# output_filter.net
KiCad netlist of a schematic drawn in Altium Designer
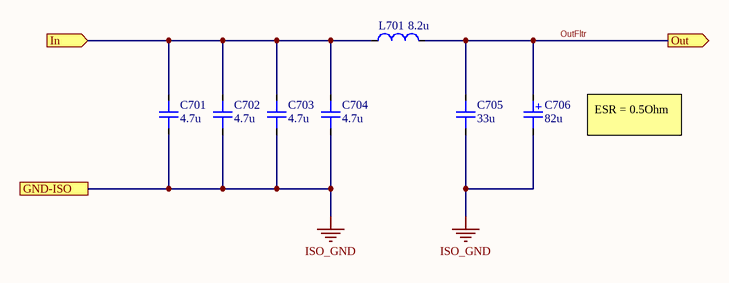
[diagram p0: output_filter.SchDoc]

(export (version "E")
  (design (tool "Eeschema 10.0.6"))
  (components
    (comp (ref "C701")
      (value "4.7u")
      (footprint "CAP1206")
      (libsource (lib "schematic_library") (part "Capacitor"))
    )
    (comp (ref "C702")
      (value "4.7u")
      (footprint "CAP1206")
      (libsource (lib "schematic_library") (part "Capacitor"))
    )
    (comp (ref "C703")
      (value "4.7u")
      (footprint "CAP1206")
      (libsource (lib "schematic_library") (part "Capacitor"))
    )
    (comp (ref "C704")
      (value "4.7u")
      (footprint "CAP1206")
      (libsource (lib "schematic_library") (part "Capacitor"))
    )
    (comp (ref "C705")
      (value "33u")
      (footprint "CAP2220")
      (libsource (lib "schematic_library") (part "Capacitor"))
    )
    (comp (ref "C706")
      (value "82u")
      (footprint "WCAP-PSLC_D8H11.7")
      (libsource (lib "schematic_library") (part "Capacitor"))
    )
    (comp (ref "L701")
      (value "8.2u")
      (footprint "FP-IHLP-3232DZ-FP_2_413x5-MFG")
      (libsource (lib "schematic_library") (part "Inductor"))
    )
  )
  (nets
    (net (code "1") (name "/In") (class "Default")
      (node (ref "C701") (pin "1") (pintype "passive"))
      (node (ref "C702") (pin "1") (pintype "passive"))
      (node (ref "C703") (pin "1") (pintype "passive"))
      (node (ref "C704") (pin "1") (pintype "passive"))
      (node (ref "L701") (pin "1") (pintype "passive"))
    )
    (net (code "2") (name "/OutFltr") (class "Default")
      (node (ref "C705") (pin "1") (pintype "passive"))
      (node (ref "C706") (pin "1") (pintype "passive"))
      (node (ref "L701") (pin "2") (pintype "passive"))
    )
    (net (code "3") (name "ISO_GND") (class "Default")
      (node (ref "C701") (pin "2") (pintype "passive"))
      (node (ref "C702") (pin "2") (pintype "passive"))
      (node (ref "C703") (pin "2") (pintype "passive"))
      (node (ref "C704") (pin "2") (pintype "passive"))
      (node (ref "C705") (pin "2") (pintype "passive"))
      (node (ref "C706") (pin "2") (pintype "passive"))
    )
  )
)
